# SME_PowerSwitch.net
KiCad netlist of a schematic drawn in Altium Designer
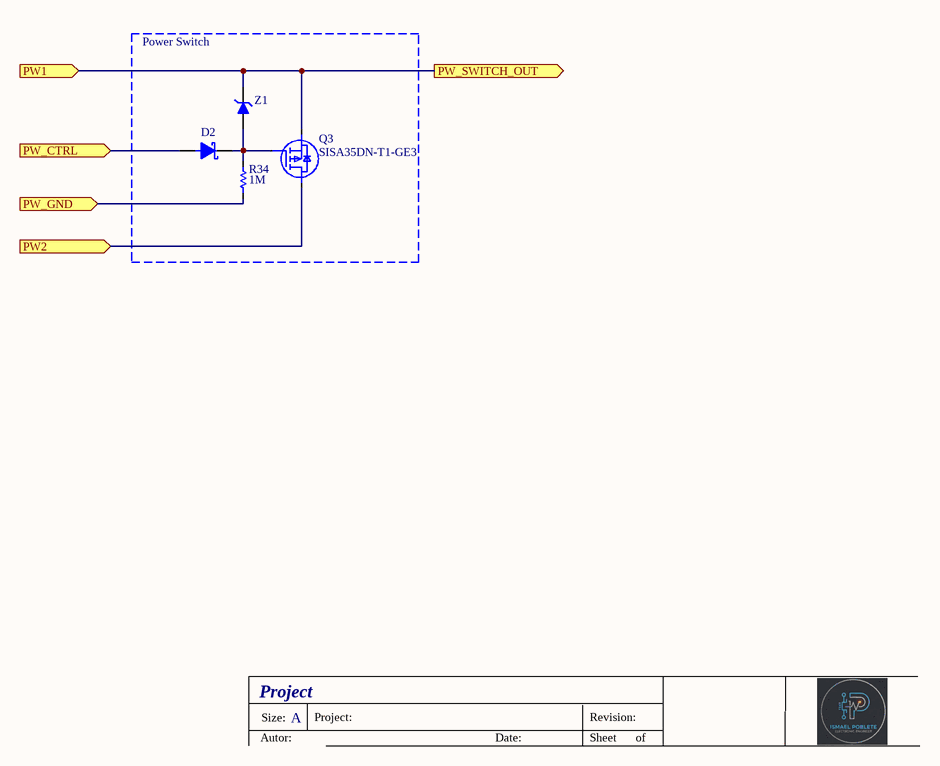
[diagram p0: SME_PowerSwitch.SchDoc]

(export (version "E")
  (design (tool "Eeschema 10.0.6"))
  (components
    (comp (ref "D2")
      (value "CDBB240-HF")
      (footprint "DO-214AA-2")
      (description "Schottky Diode")
      (fields (field (name "MOUSER PART NUMBER") "750-CDBB240-HF"))
      (libsource (lib "SME") (part "CDBB240-HF"))
    )
    (comp (ref "Q3")
      (value "SISA35DN-T1-GE3")
      (footprint "PowerPAK 1212-8-Pad")
      (description "MOSFET P-CHANNEL 30-V (D-S) PowerPAK 1212-8")
      (fields (field (name "MOUSER PART NUMBER") "78-SISA35DN-T1-GE3"))
      (libsource (lib "SME") (part "SISA35DN-T1-GE3"))
    )
    (comp (ref "R34")
      (value "RT0603FRE071ML")
      (footprint "RES_0603")
      (description "Thin Film Resistors - SMD 1M OHM 1% 50PPM 1/10 W")
      (fields (field (name "RESISTANCE") "1M"))
      (libsource (lib "SME") (part "RT0603FRE071ML"))
    )
    (comp (ref "Z1")
      (value "SZNZ8P12VMX2WT5G")
      (footprint "SOD-923")
      (description "Zener Diode")
      (libsource (lib "SME") (part "SZNZ8P12VMX2WT5G"))
    )
  )
  (nets
    (net (code "1") (name "/PW1") (class "Default")
      (node (ref "Q3") (pin "1") (pinfunction "S_1") (pintype "passive"))
      (node (ref "Z1") (pin "1") (pinfunction "K_1") (pintype "passive"))
    )
    (net (code "2") (name "/PW2") (class "Default")
      (node (ref "Q3") (pin "3") (pinfunction "D_3") (pintype "passive"))
    )
    (net (code "3") (name "/PW_CTRL") (class "Default")
      (node (ref "D2") (pin "1") (pinfunction "A_1") (pintype "passive"))
    )
    (net (code "4") (name "/PW_GND") (class "Default")
      (node (ref "R34") (pin "1") (pinfunction "1_1") (pintype "passive"))
    )
    (net (code "5") (name "Net-(D2-K)") (class "Default")
      (node (ref "D2") (pin "2") (pinfunction "K_2") (pintype "passive"))
      (node (ref "Q3") (pin "2") (pinfunction "G_2") (pintype "passive"))
      (node (ref "R34") (pin "2") (pinfunction "2_2") (pintype "passive"))
      (node (ref "Z1") (pin "2") (pinfunction "A_2") (pintype "passive"))
    )
  )
)
